# UpDuino_Camera_Adaptor_V2_0.net
KiCad netlist of a schematic drawn in Altium Designer
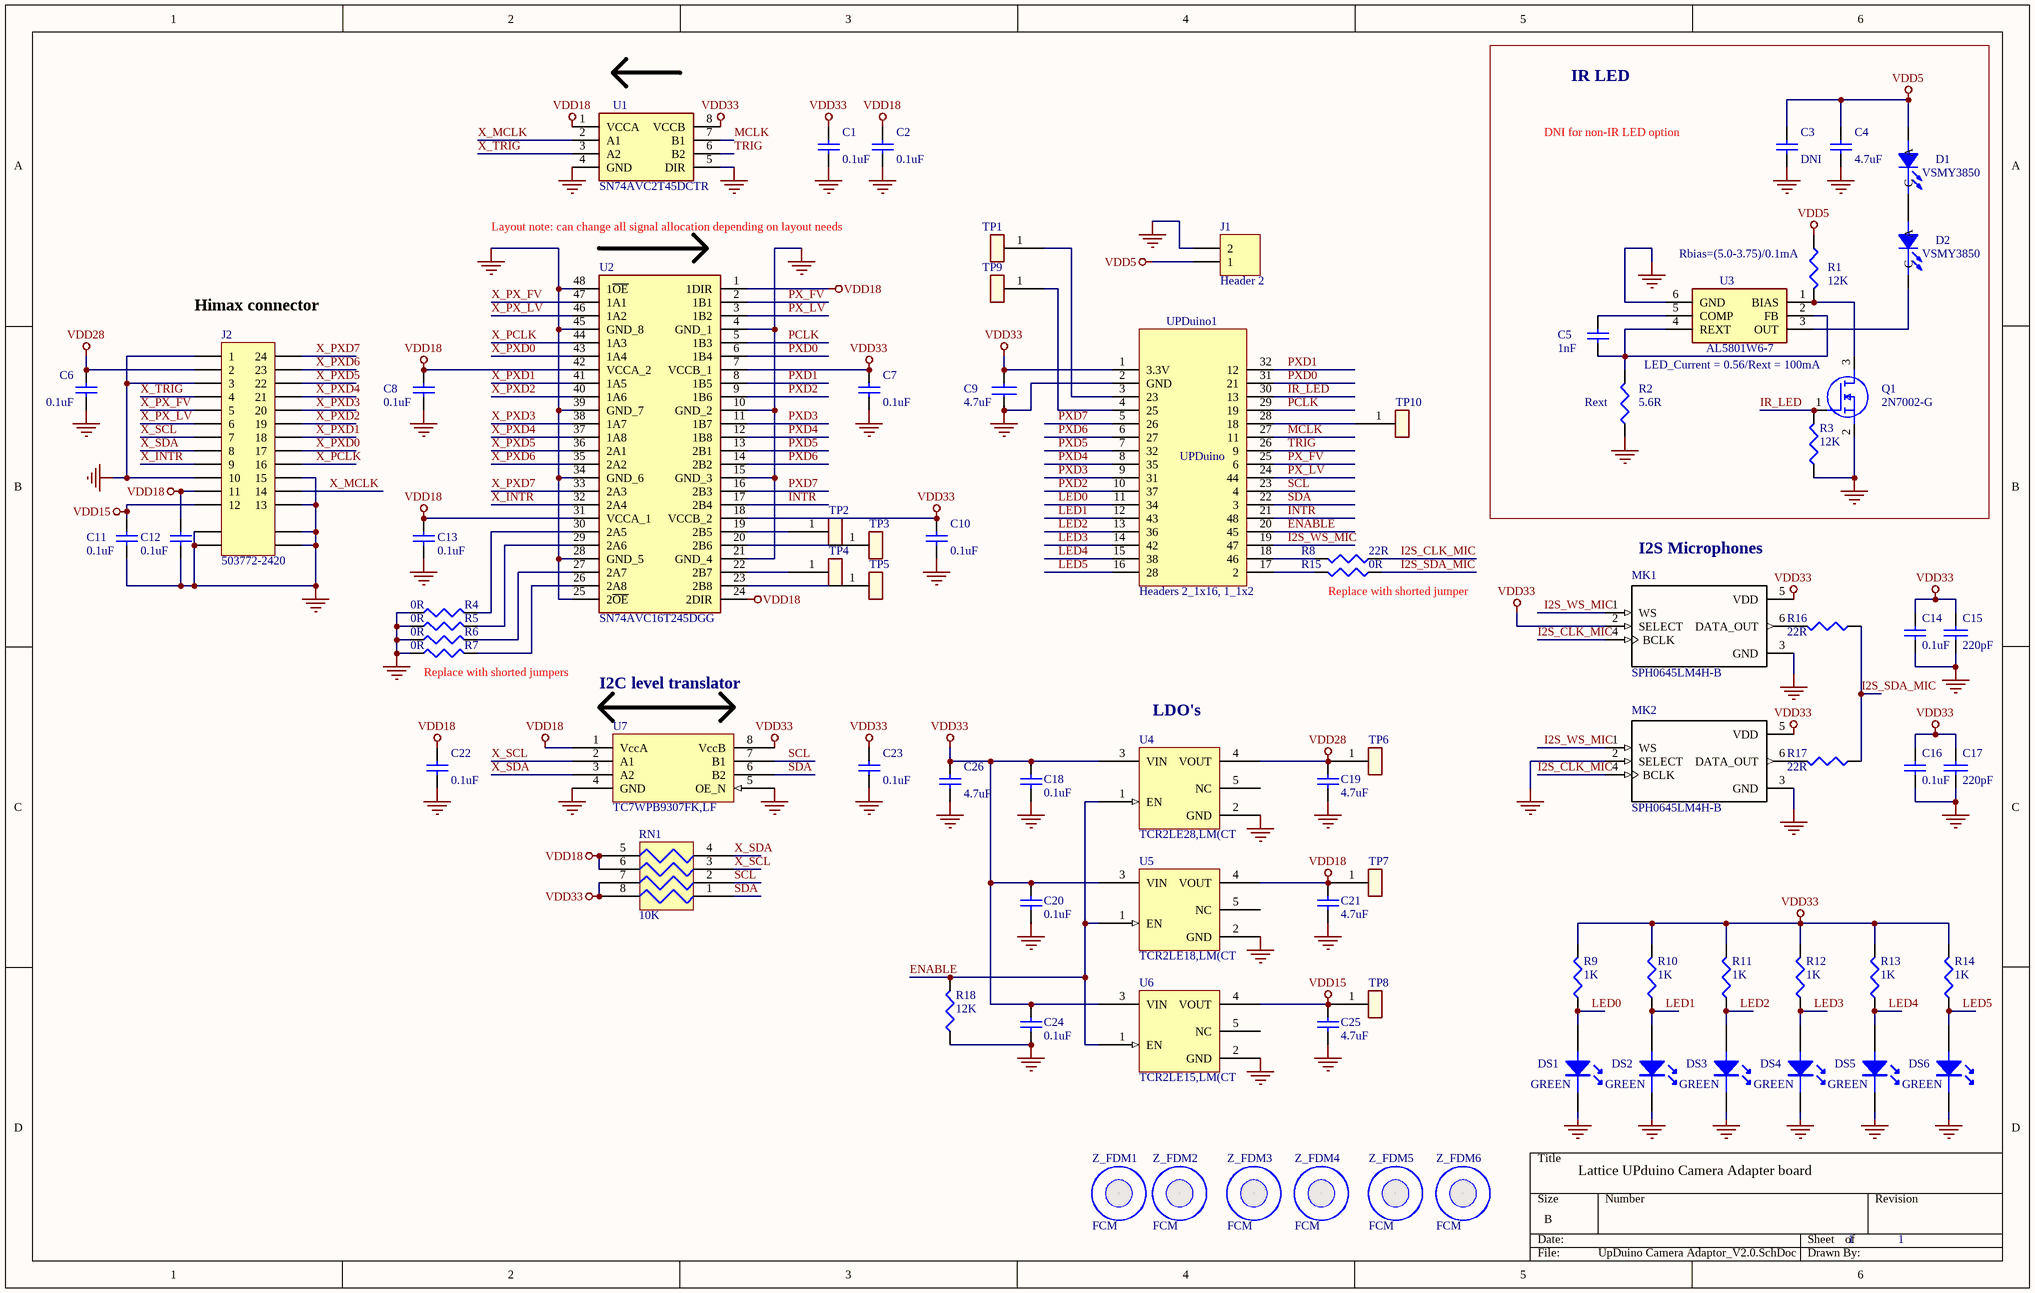
[diagram p0: UpDuino Camera Adaptor_V2.0.SchDoc]

(export (version "E")
  (design (tool "Eeschema 10.0.6"))
  (components
    (comp (ref "C1")
      (value "0.1uF")
      (footprint "C0603")
      (description "CAP CER 0.1UF 6.3V X5R 0603")
      (libsource (lib "MCD_Temp_LBE") (part "Cap_100nF_X7R_10%_0402"))
    )
    (comp (ref "C2")
      (value "0.1uF")
      (footprint "C0603")
      (description "CAP CER 0.1UF 6.3V X5R 0603")
      (libsource (lib "MCD_Temp_LBE") (part "Cap_100nF_X7R_10%_0402"))
    )
    (comp (ref "C3")
      (value "DNI")
      (footprint "C0603")
      (libsource (lib "MCD_Temp_LBE") (part "Cap_100nF_X7R_10%_0402"))
    )
    (comp (ref "C4")
      (value "4.7uF")
      (footprint "C0603")
      (description "CAP CER 4.7UF 6.3V X5R 0603")
      (libsource (lib "MCD_Temp_LBE") (part "Cap_100nF_X7R_10%_0402"))
    )
    (comp (ref "C5")
      (value "1nF")
      (footprint "C0603")
      (description "CAP CER 0.1UF 6.3V X5R 0402")
      (fields (field (name "MANUFACTURER") "TDK") (field (name "PART #") "E-CAP-003"))
      (libsource (lib "MCD_Temp_LBE") (part "Cap_100nF_X7R_10%_0402"))
    )
    (comp (ref "C6")
      (value "0.1uF")
      (footprint "C0603")
      (description "CAP CER 0.1UF 6.3V X5R 0603")
      (libsource (lib "MCD_Temp_LBE") (part "Cap_100nF_X7R_10%_0402"))
    )
    (comp (ref "C7")
      (value "0.1uF")
      (footprint "C0603")
      (description "CAP CER 0.1UF 6.3V X5R 0603")
      (libsource (lib "MCD_Temp_LBE") (part "Cap_100nF_X7R_10%_0402"))
    )
    (comp (ref "C8")
      (value "0.1uF")
      (footprint "C0603")
      (description "CAP CER 0.1UF 6.3V X5R 0402")
      (libsource (lib "MCD_Temp_LBE") (part "Cap_100nF_X7R_10%_0402"))
    )
    (comp (ref "C9")
      (value "4.7uF")
      (footprint "C0603")
      (description "4.7 uF 6.3V X5R")
      (libsource (lib "*") (part "CAP NP"))
    )
    (comp (ref "C10")
      (value "0.1uF")
      (footprint "C0603")
      (description "CAP CER 0.1UF 6.3V X5R 0603")
      (libsource (lib "MCD_Temp_LBE") (part "Cap_100nF_X7R_10%_0402"))
    )
    (comp (ref "C11")
      (value "0.1uF")
      (footprint "C0603")
      (description "CAP CER 0.1UF 6.3V X5R 0603")
      (libsource (lib "MCD_Temp_LBE") (part "Cap_100nF_X7R_10%_0402"))
    )
    (comp (ref "C12")
      (value "0.1uF")
      (footprint "C0603")
      (description "CAP CER 0.1UF 6.3V X5R 0603")
      (libsource (lib "MCD_Temp_LBE") (part "Cap_100nF_X7R_10%_0402"))
    )
    (comp (ref "C13")
      (value "0.1uF")
      (footprint "C0603")
      (description "CAP CER 0.1UF 6.3V X5R 0402")
      (libsource (lib "MCD_Temp_LBE") (part "Cap_100nF_X7R_10%_0402"))
    )
    (comp (ref "C14")
      (value "0.1uF")
      (footprint "C0603")
      (description "CAP CER 0.1UF 6.3V X5R 0603")
      (libsource (lib "MCD_Temp_LBE") (part "Cap_100nF_X7R_10%_0402"))
    )
    (comp (ref "C15") (value "220pF") (footprint "C0603") (libsource (lib "Main") (part "CAP")))
    (comp (ref "C16")
      (value "0.1uF")
      (footprint "C0603")
      (description "CAP CER 0.1UF 6.3V X5R 0603")
      (libsource (lib "MCD_Temp_LBE") (part "Cap_100nF_X7R_10%_0402"))
    )
    (comp (ref "C17") (value "220pF") (footprint "C0603") (libsource (lib "Main") (part "CAP")))
    (comp (ref "C18")
      (value "0.1uF")
      (footprint "C0603")
      (description "CAP CER 0.1UF 6.3V X5R 0603")
      (libsource (lib "MCD_Temp_LBE") (part "Cap_1uF_X5R_10%_6V3_0402"))
    )
    (comp (ref "C19")
      (value "4.7uF")
      (footprint "C0603")
      (description "CAP CER 4.7UF 6.3V X5R 0603")
      (libsource (lib "MCD_Temp_LBE") (part "Cap_1uF_X5R_10%_6V3_0402"))
    )
    (comp (ref "C20")
      (value "0.1uF")
      (footprint "C0603")
      (description "CAP CER 0.1UF 6.3V X5R 0603")
      (libsource (lib "MCD_Temp_LBE") (part "Cap_1uF_X5R_10%_6V3_0402"))
    )
    (comp (ref "C21")
      (value "4.7uF")
      (footprint "C0603")
      (description "CAP CER 4.7UF 6.3V X5R 0603")
      (libsource (lib "MCD_Temp_LBE") (part "Cap_1uF_X5R_10%_6V3_0402"))
    )
    (comp (ref "C22")
      (value "0.1uF")
      (footprint "C0603")
      (description "CAP CER 0.1UF 6.3V X5R 0603")
      (libsource (lib "MCD_Temp_LBE") (part "Cap_100nF_X7R_10%_0402"))
    )
    (comp (ref "C23")
      (value "0.1uF")
      (footprint "C0603")
      (description "CAP CER 0.1UF 6.3V X5R 0603")
      (libsource (lib "MCD_Temp_LBE") (part "Cap_100nF_X7R_10%_0402"))
    )
    (comp (ref "C24")
      (value "0.1uF")
      (footprint "C0603")
      (description "CAP CER 0.1UF 6.3V X5R 0603")
      (libsource (lib "MCD_Temp_LBE") (part "Cap_1uF_X5R_10%_6V3_0402"))
    )
    (comp (ref "C25")
      (value "4.7uF")
      (footprint "C0603")
      (description "CAP CER 4.7UF 6.3V X5R 0603")
      (libsource (lib "MCD_Temp_LBE") (part "Cap_1uF_X5R_10%_6V3_0402"))
    )
    (comp (ref "C26")
      (value "4.7uF")
      (footprint "C0603")
      (description "CAP CER 4.7UF 6.3V X5R 0603")
      (libsource (lib "MCD_Temp_LBE") (part "Cap_100nF_X7R_10%_0402"))
    )
    (comp (ref "D1")
      (value "VSMY3850")
      (footprint "PLCC-2")
      (description "EMITTER IR 850NM 70MA 3.20MM SMD")
      (fields
        (field (name "MANUFACTURER") "OSRAM Opto Semiconductors Inc.")
        (field (name "MANUFACTURER PART NUMBER") "VSMY12850")
      )
      (libsource (lib "TINYMODULE_Library") (part "LED"))
    )
    (comp (ref "D2")
      (value "VSMY3850")
      (footprint "PLCC-2")
      (description "EMITTER IR 850NM 70MA 3.20MM SMD")
      (fields
        (field (name "MANUFACTURER") "OSRAM Opto Semiconductors Inc.")
        (field (name "MANUFACTURER PART NUMBER") "VSMY12850")
      )
      (libsource (lib "TINYMODULE_Library") (part "LED"))
    )
    (comp (ref "DS1")
      (value "GREEN")
      (footprint "LED_0603_12")
      (description "Liteon LTST-C191KGKT")
      (fields (field (name "MANUFACTURER") "Avago Technologies US Inc.") (field (name "PART #") "E-MISC-005"))
      (libsource (lib "*") (part "LED_1"))
    )
    (comp (ref "DS2")
      (value "GREEN")
      (footprint "LED_0603_12")
      (description "Liteon LTST-C191KGKT")
      (fields (field (name "MANUFACTURER") "Avago Technologies US Inc.") (field (name "PART #") "E-MISC-005"))
      (libsource (lib "*") (part "LED_1"))
    )
    (comp (ref "DS3")
      (value "GREEN")
      (footprint "LED_0603_12")
      (description "Liteon LTST-C191KGKT")
      (fields (field (name "MANUFACTURER") "Avago Technologies US Inc.") (field (name "PART #") "E-MISC-005"))
      (libsource (lib "*") (part "LED_1"))
    )
    (comp (ref "DS4")
      (value "GREEN")
      (footprint "LED_0603_12")
      (description "Liteon LTST-C191KGKT")
      (fields (field (name "MANUFACTURER") "Avago Technologies US Inc.") (field (name "PART #") "E-MISC-005"))
      (libsource (lib "*") (part "LED_1"))
    )
    (comp (ref "DS5")
      (value "GREEN")
      (footprint "LED_0603_12")
      (description "Liteon LTST-C191KGKT")
      (fields (field (name "MANUFACTURER") "Avago Technologies US Inc.") (field (name "PART #") "E-MISC-005"))
      (libsource (lib "*") (part "LED_1"))
    )
    (comp (ref "DS6")
      (value "GREEN")
      (footprint "LED_0603_12")
      (description "Liteon LTST-C191KGKT")
      (fields (field (name "MANUFACTURER") "Avago Technologies US Inc.") (field (name "PART #") "E-MISC-005"))
      (libsource (lib "*") (part "LED_1"))
    )
    (comp (ref "J1")
      (value "Header 2")
      (footprint "HDR1X2")
      (description "Header, 2-Pin")
      (fields (field (name "PUBLISHER") "Altium Limited"))
      (libsource (lib "Miscellaneous Connectors") (part "Header 2"))
    )
    (comp (ref "J2")
      (value "503772-2420")
      (footprint "MOLEX-5037722410_MOLEX")
      (description "Header, 12-Pin, Dual row")
      (fields
        (field (name "MANUFACTURER") "Amphenol FCI")
        (field (name "MANUFACTURER PART NUMBER") "SFV24R-3STE1HLF")
        (field (name "PUBLISHER") "Altium Limited")
      )
      (libsource (lib "UpDuino Camera Adaptor_V2.0") (part "Header 12X2A"))
    )
    (comp (ref "MK1")
      (value "SPH0645LM4H-B")
      (footprint "*MIC_SPH0645LM4H-B")
      (description "Mic Mems Digital I2s Omni -26db")
      (fields (field (name "MFR") "Knowles") (field (name "DIGI-KEY_PART_NUMBER") "423-1405-1-ND"))
      (libsource (lib "SPH0645LM4H-B") (part "SPH0645LM4H-B"))
    )
    (comp (ref "MK2")
      (value "SPH0645LM4H-B")
      (footprint "*MIC_SPH0645LM4H-B")
      (description "Mic Mems Digital I2s Omni -26db")
      (fields (field (name "MFR") "Knowles") (field (name "DIGI-KEY_PART_NUMBER") "423-1405-1-ND"))
      (libsource (lib "SPH0645LM4H-B") (part "SPH0645LM4H-B"))
    )
    (comp (ref "Q1")
      (value "2N7002-G")
      (footprint "SOT23-3")
      (description "MOSFET (N-Channel)")
      (fields (field (name "MOUSER PART NUMBER") "750-2N7002-G"))
      (libsource (lib "*") (part "2N7002-G"))
    )
    (comp (ref "R1") (value "12K") (footprint "R0603") (libsource (lib "*") (part "R_SH")))
    (comp (ref "R2") (value "5.6R") (footprint "R0603") (libsource (lib "*") (part "R_SH")))
    (comp (ref "R3") (value "12K") (footprint "R0603") (libsource (lib "*") (part "R_SH")))
    (comp (ref "R4") (value "0R") (footprint "SB_0603") (libsource (lib "*") (part "R_SH")))
    (comp (ref "R5") (value "0R") (footprint "SB_0603") (libsource (lib "*") (part "R_SH")))
    (comp (ref "R6") (value "0R") (footprint "SB_0603") (libsource (lib "*") (part "R_SH")))
    (comp (ref "R7") (value "0R") (footprint "SB_0603") (libsource (lib "*") (part "R_SH")))
    (comp (ref "R8") (value "22R") (footprint "R0603") (libsource (lib "*") (part "R_SH")))
    (comp (ref "R9") (value "1K") (footprint "R0603") (libsource (lib "*") (part "R_SH")))
    (comp (ref "R10") (value "1K") (footprint "R0603") (libsource (lib "*") (part "R_SH")))
    (comp (ref "R11") (value "1K") (footprint "R0603") (libsource (lib "*") (part "R_SH")))
    (comp (ref "R12") (value "1K") (footprint "R0603") (libsource (lib "*") (part "R_SH")))
    (comp (ref "R13") (value "1K") (footprint "R0603") (libsource (lib "*") (part "R_SH")))
    (comp (ref "R14") (value "1K") (footprint "R0603") (libsource (lib "*") (part "R_SH")))
    (comp (ref "R15") (value "0R") (footprint "SB_0603") (libsource (lib "*") (part "R_SH")))
    (comp (ref "R16") (value "22R") (footprint "R0603") (libsource (lib "*") (part "R_SH")))
    (comp (ref "R17") (value "22R") (footprint "R0603") (libsource (lib "*") (part "R_SH")))
    (comp (ref "R18") (value "12K") (footprint "R0603") (libsource (lib "*") (part "R_SH")))
    (comp (ref "RN1")
      (value "10K")
      (footprint "RN4(0402)")
      (description "EXB-28V104JX")
      (libsource (lib "main") (part "EXB28V"))
    )
    (comp (ref "TP1") (value "TEST POINT") (footprint "TP_SMD_D1") (libsource (lib "") (part "TEST POINT_1")))
    (comp (ref "TP2") (value "TEST POINT") (footprint "TP_SMD_D1") (libsource (lib "*") (part "TEST POINT")))
    (comp (ref "TP3") (value "TEST POINT") (footprint "TP_SMD_D1") (libsource (lib "*") (part "TEST POINT")))
    (comp (ref "TP4") (value "TEST POINT") (footprint "TP_SMD_D1") (libsource (lib "*") (part "TEST POINT")))
    (comp (ref "TP5") (value "TEST POINT") (footprint "TP_SMD_D1") (libsource (lib "*") (part "TEST POINT")))
    (comp (ref "TP6") (value "TEST POINT") (footprint "TP_SMD_D1") (libsource (lib "*") (part "TEST POINT")))
    (comp (ref "TP7") (value "TEST POINT") (footprint "TP_SMD_D1") (libsource (lib "*") (part "TEST POINT")))
    (comp (ref "TP8") (value "TEST POINT") (footprint "TP_SMD_D1") (libsource (lib "*") (part "TEST POINT")))
    (comp (ref "TP9") (value "TEST POINT") (footprint "TP_SMD_D1") (libsource (lib "") (part "TEST POINT_1")))
    (comp (ref "TP10") (value "TEST POINT") (footprint "TP_SMD_D1") (libsource (lib "*") (part "TEST POINT")))
    (comp (ref "U1")
      (value "SN74AVC2T45DCTR")
      (footprint "MSOP-8(2.95x2.80)")
      (description "Integrated Circuit")
      (fields
        (field (name "MOUSER PART NUMBER") "595-SN74AVC2T45DCTR")
        (field (name "RS PART NUMBER") "8253432P")
      )
      (libsource (lib "*") (part "SN74AVC2T45DCTR"))
    )
    (comp (ref "U2")
      (value "SN74AVC16T245DGG")
      (footprint "TSSOP-48")
      (description "Integrated Circuit")
      (fields (field (name "MOUSER PART NUMBER") "595-SN74AVC16T245DG"))
      (libsource (lib "*") (part "SN74AVC16T245DGG"))
    )
    (comp (ref "U3")
      (value "AL5801W6-7")
      (footprint "SOT-23-6-(SSOT-6)")
      (description "Integrated Circuit")
      (fields (field (name "MOUSER PART NUMBER") "621-AL5801W6-7") (field (name "RS PART NUMBER") "8228732P"))
      (libsource (lib "*") (part "AL5801W6-7"))
    )
    (comp (ref "U4")
      (value "TCR2LE28,LM(CT")
      (footprint "SOT-553")
      (libsource (lib "TINYMODULE") (part "TCR2LE12ESV"))
    )
    (comp (ref "U5")
      (value "TCR2LE18,LM(CT")
      (footprint "SOT-553")
      (libsource (lib "TINYMODULE") (part "TCR2LE12ESV"))
    )
    (comp (ref "U6")
      (value "TCR2LE15,LM(CT")
      (footprint "SOT-553")
      (libsource (lib "TINYMODULE") (part "TCR2LE12ESV"))
    )
    (comp (ref "U7")
      (value "TC7WPB9307FK,LF")
      (footprint "SSOP8-P-0.50A")
      (description "Dual bidirectional level translator")
      (libsource (lib "tinyVision") (part "TC7WPB9307FK"))
    )
    (comp (ref "UPDuino1")
      (value "Headers 2_1x16, 1_1x2")
      (footprint "UPDuino-SMD")
      (description "UPDuino Breakout Headers")
      (fields (field (name "MFR PART NO.") "HWS15774, HWS15768") (field (name "MFR") "Phoenix contact"))
      (libsource (lib "one_wire") (part "UPDuino_Breakout"))
    )
    (comp (ref "Z_FDM1") (value "FCM") (footprint "FID100X250N") (libsource (lib "LCD-TN43") (part "FCM")))
    (comp (ref "Z_FDM2") (value "FCM") (footprint "FID100X250N") (libsource (lib "LCD-TN43") (part "FCM")))
    (comp (ref "Z_FDM3") (value "FCM") (footprint "FID100X250N") (libsource (lib "LCD-TN43") (part "FCM")))
    (comp (ref "Z_FDM4") (value "FCM") (footprint "FID100X250N") (libsource (lib "LCD-TN43") (part "FCM")))
    (comp (ref "Z_FDM5") (value "FCM") (footprint "FID100X250N") (libsource (lib "LCD-TN43") (part "FCM")))
    (comp (ref "Z_FDM6") (value "FCM") (footprint "FID100X250N") (libsource (lib "LCD-TN43") (part "FCM")))
  )
  (nets
    (net (code "1") (name "/ENABLE") (class "Default")
      (node (ref "R18") (pin "2") (pinfunction "2_2") (pintype "passive"))
      (node (ref "U4") (pin "1") (pinfunction "EN_1") (pintype "input"))
      (node (ref "U5") (pin "1") (pinfunction "EN_1") (pintype "input"))
      (node (ref "U6") (pin "1") (pinfunction "EN_1") (pintype "input"))
      (node (ref "UPDuino1") (pin "20") (pinfunction "45_20") (pintype "passive"))
    )
    (net (code "2") (name "/I2S_CLK_MIC") (class "Default")
      (node (ref "MK1") (pin "4") (pinfunction "BCLK_4") (pintype "input"))
      (node (ref "MK2") (pin "4") (pinfunction "BCLK_4") (pintype "input"))
      (node (ref "R8") (pin "1") (pinfunction "1_1") (pintype "passive"))
    )
    (net (code "3") (name "/I2S_SDA_MIC") (class "Default")
      (node (ref "R15") (pin "1") (pinfunction "1_1") (pintype "passive"))
      (node (ref "R16") (pin "1") (pinfunction "1_1") (pintype "passive"))
      (node (ref "R17") (pin "1") (pinfunction "1_1") (pintype "passive"))
    )
    (net (code "4") (name "/I2S_WS_MIC") (class "Default")
      (node (ref "MK1") (pin "1") (pinfunction "WS_1") (pintype "input"))
      (node (ref "MK2") (pin "1") (pinfunction "WS_1") (pintype "input"))
      (node (ref "UPDuino1") (pin "19") (pinfunction "47_19") (pintype "passive"))
    )
    (net (code "5") (name "/INTR") (class "Default")
      (node (ref "U2") (pin "17") (pinfunction "2B4_17") (pintype "passive"))
      (node (ref "UPDuino1") (pin "21") (pinfunction "48_21") (pintype "passive"))
    )
    (net (code "6") (name "/IR_LED") (class "Default")
      (node (ref "Q1") (pin "1") (pinfunction "G_1") (pintype "passive"))
      (node (ref "R3") (pin "2") (pinfunction "2_2") (pintype "passive"))
      (node (ref "UPDuino1") (pin "30") (pinfunction "13_30") (pintype "passive"))
    )
    (net (code "7") (name "/LED0") (class "Default")
      (node (ref "DS1") (pin "1") (pinfunction "1_1") (pintype "passive"))
      (node (ref "R9") (pin "1") (pinfunction "1_1") (pintype "passive"))
      (node (ref "UPDuino1") (pin "11") (pinfunction "34_11") (pintype "passive"))
    )
    (net (code "8") (name "/LED1") (class "Default")
      (node (ref "DS2") (pin "1") (pinfunction "1_1") (pintype "passive"))
      (node (ref "R10") (pin "1") (pinfunction "1_1") (pintype "passive"))
      (node (ref "UPDuino1") (pin "12") (pinfunction "43_12") (pintype "passive"))
    )
    (net (code "9") (name "/LED2") (class "Default")
      (node (ref "DS3") (pin "1") (pinfunction "1_1") (pintype "passive"))
      (node (ref "R11") (pin "1") (pinfunction "1_1") (pintype "passive"))
      (node (ref "UPDuino1") (pin "13") (pinfunction "36_13") (pintype "passive"))
    )
    (net (code "10") (name "/LED3") (class "Default")
      (node (ref "DS4") (pin "1") (pinfunction "1_1") (pintype "passive"))
      (node (ref "R12") (pin "1") (pinfunction "1_1") (pintype "passive"))
      (node (ref "UPDuino1") (pin "14") (pinfunction "42_14") (pintype "passive"))
    )
    (net (code "11") (name "/LED4") (class "Default")
      (node (ref "DS5") (pin "1") (pinfunction "1_1") (pintype "passive"))
      (node (ref "R13") (pin "1") (pinfunction "1_1") (pintype "passive"))
      (node (ref "UPDuino1") (pin "15") (pinfunction "38_15") (pintype "passive"))
    )
    (net (code "12") (name "/LED5") (class "Default")
      (node (ref "DS6") (pin "1") (pinfunction "1_1") (pintype "passive"))
      (node (ref "R14") (pin "1") (pinfunction "1_1") (pintype "passive"))
      (node (ref "UPDuino1") (pin "16") (pinfunction "28_16") (pintype "passive"))
    )
    (net (code "13") (name "/MCLK") (class "Default")
      (node (ref "U1") (pin "7") (pinfunction "B1_7") (pintype "passive"))
      (node (ref "UPDuino1") (pin "27") (pinfunction "11_27") (pintype "passive"))
    )
    (net (code "14") (name "/PCLK") (class "Default")
      (node (ref "U2") (pin "5") (pinfunction "1B3_5") (pintype "passive"))
      (node (ref "UPDuino1") (pin "29") (pinfunction "19_29") (pintype "passive"))
    )
    (net (code "15") (name "/PXD0") (class "Default")
      (node (ref "U2") (pin "6") (pinfunction "1B4_6") (pintype "passive"))
      (node (ref "UPDuino1") (pin "31") (pinfunction "21_31") (pintype "passive"))
    )
    (net (code "16") (name "/PXD1") (class "Default")
      (node (ref "U2") (pin "8") (pinfunction "1B5_8") (pintype "passive"))
      (node (ref "UPDuino1") (pin "32") (pinfunction "12_32") (pintype "passive"))
    )
    (net (code "17") (name "/PXD2") (class "Default")
      (node (ref "U2") (pin "9") (pinfunction "1B6_9") (pintype "passive"))
      (node (ref "UPDuino1") (pin "10") (pinfunction "37_10") (pintype "passive"))
    )
    (net (code "18") (name "/PXD3") (class "Default")
      (node (ref "U2") (pin "11") (pinfunction "1B7_11") (pintype "passive"))
      (node (ref "UPDuino1") (pin "9") (pinfunction "31_9") (pintype "passive"))
    )
    (net (code "19") (name "/PXD4") (class "Default")
      (node (ref "U2") (pin "12") (pinfunction "1B8_12") (pintype "passive"))
      (node (ref "UPDuino1") (pin "8") (pinfunction "35_8") (pintype "passive"))
    )
    (net (code "20") (name "/PXD5") (class "Default")
      (node (ref "U2") (pin "13") (pinfunction "2B1_13") (pintype "passive"))
      (node (ref "UPDuino1") (pin "7") (pinfunction "32_7") (pintype "passive"))
    )
    (net (code "21") (name "/PXD6") (class "Default")
      (node (ref "U2") (pin "14") (pinfunction "2B2_14") (pintype "passive"))
      (node (ref "UPDuino1") (pin "6") (pinfunction "27_6") (pintype "passive"))
    )
    (net (code "22") (name "/PXD7") (class "Default")
      (node (ref "U2") (pin "16") (pinfunction "2B3_16") (pintype "passive"))
      (node (ref "UPDuino1") (pin "5") (pinfunction "26_5") (pintype "passive"))
    )
    (net (code "23") (name "/PX_FV") (class "Default")
      (node (ref "U2") (pin "2") (pinfunction "1B1_2") (pintype "passive"))
      (node (ref "UPDuino1") (pin "25") (pinfunction "6_25") (pintype "passive"))
    )
    (net (code "24") (name "/PX_LV") (class "Default")
      (node (ref "U2") (pin "3") (pinfunction "1B2_3") (pintype "passive"))
      (node (ref "UPDuino1") (pin "24") (pinfunction "44_24") (pintype "passive"))
    )
    (net (code "25") (name "/SCL") (class "Default")
      (node (ref "RN1") (pin "2") (pintype "passive"))
      (node (ref "U7") (pin "7") (pinfunction "B1_7") (pintype "passive"))
      (node (ref "UPDuino1") (pin "23") (pinfunction "4_23") (pintype "passive"))
    )
    (net (code "26") (name "/SDA") (class "Default")
      (node (ref "RN1") (pin "1") (pintype "passive"))
      (node (ref "U7") (pin "6") (pinfunction "B2_6") (pintype "passive"))
      (node (ref "UPDuino1") (pin "22") (pinfunction "3_22") (pintype "passive"))
    )
    (net (code "27") (name "/TRIG") (class "Default")
      (node (ref "U1") (pin "6") (pinfunction "B2_6") (pintype "passive"))
      (node (ref "UPDuino1") (pin "26") (pinfunction "9_26") (pintype "passive"))
    )
    (net (code "28") (name "/X_INTR") (class "Default")
      (node (ref "J2") (pin "9") (pinfunction "9_9") (pintype "passive"))
      (node (ref "U2") (pin "32") (pinfunction "2A4_32") (pintype "passive"))
    )
    (net (code "29") (name "/X_MCLK") (class "Default")
      (node (ref "J2") (pin "14") (pinfunction "14_14") (pintype "passive"))
      (node (ref "U1") (pin "2") (pinfunction "A1_2") (pintype "passive"))
    )
    (net (code "30") (name "/X_PCLK") (class "Default")
      (node (ref "J2") (pin "16") (pinfunction "16_16") (pintype "passive"))
      (node (ref "U2") (pin "44") (pinfunction "1A3_44") (pintype "passive"))
    )
    (net (code "31") (name "/X_PXD0") (class "Default")
      (node (ref "J2") (pin "17") (pinfunction "17_17") (pintype "passive"))
      (node (ref "U2") (pin "43") (pinfunction "1A4_43") (pintype "passive"))
    )
    (net (code "32") (name "/X_PXD1") (class "Default")
      (node (ref "J2") (pin "18") (pinfunction "18_18") (pintype "passive"))
      (node (ref "U2") (pin "41") (pinfunction "1A5_41") (pintype "passive"))
    )
    (net (code "33") (name "/X_PXD2") (class "Default")
      (node (ref "J2") (pin "19") (pinfunction "19_19") (pintype "passive"))
      (node (ref "U2") (pin "40") (pinfunction "1A6_40") (pintype "passive"))
    )
    (net (code "34") (name "/X_PXD3") (class "Default")
      (node (ref "J2") (pin "20") (pinfunction "20_20") (pintype "passive"))
      (node (ref "U2") (pin "38") (pinfunction "1A7_38") (pintype "passive"))
    )
    (net (code "35") (name "/X_PXD4") (class "Default")
      (node (ref "J2") (pin "21") (pinfunction "21_21") (pintype "passive"))
      (node (ref "U2") (pin "37") (pinfunction "1A8_37") (pintype "passive"))
    )
    (net (code "36") (name "/X_PXD5") (class "Default")
      (node (ref "J2") (pin "22") (pinfunction "22_22") (pintype "passive"))
      (node (ref "U2") (pin "36") (pinfunction "2A1_36") (pintype "passive"))
    )
    (net (code "37") (name "/X_PXD6") (class "Default")
      (node (ref "J2") (pin "23") (pinfunction "23_23") (pintype "passive"))
      (node (ref "U2") (pin "35") (pinfunction "2A2_35") (pintype "passive"))
    )
    (net (code "38") (name "/X_PXD7") (class "Default")
      (node (ref "J2") (pin "24") (pinfunction "24_24") (pintype "passive"))
      (node (ref "U2") (pin "33") (pinfunction "2A3_33") (pintype "passive"))
    )
    (net (code "39") (name "/X_PX_FV") (class "Default")
      (node (ref "J2") (pin "5") (pinfunction "5_5") (pintype "passive"))
      (node (ref "U2") (pin "47") (pinfunction "1A1_47") (pintype "passive"))
    )
    (net (code "40") (name "/X_PX_LV") (class "Default")
      (node (ref "J2") (pin "6") (pinfunction "6_6") (pintype "passive"))
      (node (ref "U2") (pin "46") (pinfunction "1A2_46") (pintype "passive"))
    )
    (net (code "41") (name "/X_SCL") (class "Default")
      (node (ref "J2") (pin "7") (pinfunction "7_7") (pintype "passive"))
      (node (ref "RN1") (pin "3") (pintype "passive"))
      (node (ref "U7") (pin "2") (pinfunction "A1_2") (pintype "passive"))
    )
    (net (code "42") (name "/X_SDA") (class "Default")
      (node (ref "J2") (pin "8") (pinfunction "8_8") (pintype "passive"))
      (node (ref "RN1") (pin "4") (pintype "passive"))
      (node (ref "U7") (pin "3") (pinfunction "A2_3") (pintype "passive"))
    )
    (net (code "43") (name "/X_TRIG") (class "Default")
      (node (ref "J2") (pin "4") (pinfunction "4_4") (pintype "passive"))
      (node (ref "U1") (pin "3") (pinfunction "A2_3") (pintype "passive"))
    )
    (net (code "44") (name "GND") (class "Default")
      (node (ref "C1") (pin "2") (pinfunction "2_2") (pintype "passive"))
      (node (ref "C10") (pin "2") (pinfunction "2_2") (pintype "passive"))
      (node (ref "C11") (pin "2") (pinfunction "2_2") (pintype "passive"))
      (node (ref "C12") (pin "2") (pinfunction "2_2") (pintype "passive"))
      (node (ref "C13") (pin "2") (pinfunction "2_2") (pintype "passive"))
      (node (ref "C14") (pin "2") (pinfunction "2_2") (pintype "passive"))
      (node (ref "C15") (pin "2") (pinfunction "2_2") (pintype "passive"))
      (node (ref "C16") (pin "2") (pinfunction "2_2") (pintype "passive"))
      (node (ref "C17") (pin "2") (pinfunction "2_2") (pintype "passive"))
      (node (ref "C18") (pin "1") (pinfunction "1_1") (pintype "passive"))
      (node (ref "C19") (pin "1") (pinfunction "1_1") (pintype "passive"))
      (node (ref "C2") (pin "2") (pinfunction "2_2") (pintype "passive"))
      (node (ref "C20") (pin "1") (pinfunction "1_1") (pintype "passive"))
      (node (ref "C21") (pin "1") (pinfunction "1_1") (pintype "passive"))
      (node (ref "C22") (pin "2") (pinfunction "2_2") (pintype "passive"))
      (node (ref "C23") (pin "2") (pinfunction "2_2") (pintype "passive"))
      (node (ref "C24") (pin "1") (pinfunction "1_1") (pintype "passive"))
      (node (ref "C25") (pin "1") (pinfunction "1_1") (pintype "passive"))
      (node (ref "C26") (pin "2") (pinfunction "2_2") (pintype "passive"))
      (node (ref "C3") (pin "2") (pinfunction "2_2") (pintype "passive"))
      (node (ref "C4") (pin "2") (pinfunction "2_2") (pintype "passive"))
      (node (ref "C6") (pin "2") (pinfunction "2_2") (pintype "passive"))
      (node (ref "C7") (pin "2") (pinfunction "2_2") (pintype "passive"))
      (node (ref "C8") (pin "2") (pinfunction "2_2") (pintype "passive"))
      (node (ref "C9") (pin "1") (pinfunction "1_1") (pintype "passive"))
      (node (ref "DS1") (pin "2") (pinfunction "2_2") (pintype "passive"))
      (node (ref "DS2") (pin "2") (pinfunction "2_2") (pintype "passive"))
      (node (ref "DS3") (pin "2") (pinfunction "2_2") (pintype "passive"))
      (node (ref "DS4") (pin "2") (pinfunction "2_2") (pintype "passive"))
      (node (ref "DS5") (pin "2") (pinfunction "2_2") (pintype "passive"))
      (node (ref "DS6") (pin "2") (pinfunction "2_2") (pintype "passive"))
      (node (ref "J1") (pin "2") (pinfunction "2_2") (pintype "passive"))
      (node (ref "J2") (pin "1") (pinfunction "1_1") (pintype "passive"))
      (node (ref "J2") (pin "10") (pinfunction "10_10") (pintype "passive"))
      (node (ref "J2") (pin "13") (pinfunction "13_13") (pintype "passive"))
      (node (ref "J2") (pin "15") (pinfunction "15_15") (pintype "passive"))
      (node (ref "J2") (pin "3") (pinfunction "3_3") (pintype "passive"))
      (node (ref "J2") (pin "GND1") (pinfunction "GND1_GND1") (pintype "passive"))
      (node (ref "J2") (pin "GND2") (pinfunction "GND2_GND2") (pintype "passive"))
      (node (ref "J2") (pin "GND3") (pinfunction "GND3_GND3") (pintype "passive"))
      (node (ref "J2") (pin "GND4") (pinfunction "GND4_GND4") (pintype "passive"))
      (node (ref "MK1") (pin "3") (pinfunction "GND_3") (pintype "power_in"))
      (node (ref "MK2") (pin "2") (pinfunction "SELECT_2") (pintype "input"))
      (node (ref "MK2") (pin "3") (pinfunction "GND_3") (pintype "power_in"))
      (node (ref "Q1") (pin "2") (pinfunction "S_2") (pintype "passive"))
      (node (ref "R18") (pin "1") (pinfunction "1_1") (pintype "passive"))
      (node (ref "R2") (pin "2") (pinfunction "2_2") (pintype "passive"))
      (node (ref "R3") (pin "1") (pinfunction "1_1") (pintype "passive"))
      (node (ref "R4") (pin "2") (pinfunction "2_2") (pintype "passive"))
      (node (ref "R5") (pin "2") (pinfunction "2_2") (pintype "passive"))
      (node (ref "R6") (pin "2") (pinfunction "2_2") (pintype "passive"))
      (node (ref "R7") (pin "2") (pinfunction "2_2") (pintype "passive"))
      (node (ref "U1") (pin "4") (pinfunction "GND_4") (pintype "power_in"))
      (node (ref "U1") (pin "5") (pinfunction "DIR_5") (pintype "passive"))
      (node (ref "U2") (pin "10") (pinfunction "GND_2_10") (pintype "passive"))
      (node (ref "U2") (pin "15") (pinfunction "GND_3_15") (pintype "passive"))
      (node (ref "U2") (pin "21") (pinfunction "GND_4_21") (pintype "passive"))
      (node (ref "U2") (pin "25") (pinfunction "2~{OE}_25") (pintype "passive"))
      (node (ref "U2") (pin "28") (pinfunction "GND_5_28") (pintype "passive"))
      (node (ref "U2") (pin "34") (pinfunction "GND_6_34") (pintype "passive"))
      (node (ref "U2") (pin "39") (pinfunction "GND_7_39") (pintype "passive"))
      (node (ref "U2") (pin "4") (pinfunction "GND_1_4") (pintype "passive"))
      (node (ref "U2") (pin "45") (pinfunction "GND_8_45") (pintype "passive"))
      (node (ref "U2") (pin "48") (pinfunction "1~{OE}_48") (pintype "passive"))
      (node (ref "U3") (pin "6") (pinfunction "GND_6") (pintype "passive"))
      (node (ref "U4") (pin "2") (pinfunction "GND_2") (pintype "power_in"))
      (node (ref "U5") (pin "2") (pinfunction "GND_2") (pintype "power_in"))
      (node (ref "U6") (pin "2") (pinfunction "GND_2") (pintype "power_in"))
      (node (ref "U7") (pin "4") (pinfunction "GND_4") (pintype "power_in"))
      (node (ref "U7") (pin "5") (pinfunction "OE_N_5") (pintype "input"))
      (node (ref "UPDuino1") (pin "2") (pinfunction "GND_2") (pintype "passive"))
    )
    (net (code "45") (name "Net-(D1-PadC)") (class "Default")
      (node (ref "D1") (pin "C") (pinfunction "C_C") (pintype "passive"))
      (node (ref "D2") (pin "A") (pinfunction "A_A") (pintype "passive"))
    )
    (net (code "46") (name "Net-(MK1-DATA_OUT)") (class "Default")
      (node (ref "MK1") (pin "6") (pinfunction "DATA_OUT_6") (pintype "output"))
      (node (ref "R16") (pin "2") (pinfunction "2_2") (pintype "passive"))
    )
    (net (code "47") (name "Net-(MK2-DATA_OUT)") (class "Default")
      (node (ref "MK2") (pin "6") (pinfunction "DATA_OUT_6") (pintype "output"))
      (node (ref "R17") (pin "2") (pinfunction "2_2") (pintype "passive"))
    )
    (net (code "48") (name "Net-(Q1-D)") (class "Default")
      (node (ref "Q1") (pin "3") (pinfunction "D_3") (pintype "passive"))
      (node (ref "R1") (pin "1") (pinfunction "1_1") (pintype "passive"))
      (node (ref "U3") (pin "1") (pinfunction "BIAS_1") (pintype "passive"))
    )
    (net (code "49") (name "Net-(U2-2A5)") (class "Default")
      (node (ref "R4") (pin "1") (pinfunction "1_1") (pintype "passive"))
      (node (ref "U2") (pin "30") (pinfunction "2A5_30") (pintype "passive"))
    )
    (net (code "50") (name "Net-(U2-2A6)") (class "Default")
      (node (ref "R5") (pin "1") (pinfunction "1_1") (pintype "passive"))
      (node (ref "U2") (pin "29") (pinfunction "2A6_29") (pintype "passive"))
    )
    (net (code "51") (name "Net-(U2-2A7)") (class "Default")
      (node (ref "R6") (pin "1") (pinfunction "1_1") (pintype "passive"))
      (node (ref "U2") (pin "27") (pinfunction "2A7_27") (pintype "passive"))
    )
    (net (code "52") (name "Net-(U2-2A8)") (class "Default")
      (node (ref "R7") (pin "1") (pinfunction "1_1") (pintype "passive"))
      (node (ref "U2") (pin "26") (pinfunction "2A8_26") (pintype "passive"))
    )
    (net (code "53") (name "Net-(U2-2B5)") (class "Default")
      (node (ref "TP2") (pin "1") (pinfunction "1_1") (pintype "passive"))
      (node (ref "U2") (pin "19") (pinfunction "2B5_19") (pintype "passive"))
    )
    (net (code "54") (name "Net-(U2-2B6)") (class "Default")
      (node (ref "TP3") (pin "1") (pinfunction "1_1") (pintype "passive"))
      (node (ref "U2") (pin "20") (pinfunction "2B6_20") (pintype "passive"))
    )
    (net (code "55") (name "Net-(U2-2B7)") (class "Default")
      (node (ref "TP4") (pin "1") (pinfunction "1_1") (pintype "passive"))
      (node (ref "U2") (pin "22") (pinfunction "2B7_22") (pintype "passive"))
    )
    (net (code "56") (name "Net-(U2-2B8)") (class "Default")
      (node (ref "TP5") (pin "1") (pinfunction "1_1") (pintype "passive"))
      (node (ref "U2") (pin "23") (pinfunction "2B8_23") (pintype "passive"))
    )
    (net (code "57") (name "Net-(U3-COMP)") (class "Default")
      (node (ref "C5") (pin "1") (pinfunction "1_1") (pintype "passive"))
      (node (ref "U3") (pin "5") (pinfunction "COMP_5") (pintype "passive"))
    )
    (net (code "58") (name "Net-(U3-FB)") (class "Default")
      (node (ref "C5") (pin "2") (pinfunction "2_2") (pintype "passive"))
      (node (ref "R2") (pin "1") (pinfunction "1_1") (pintype "passive"))
      (node (ref "U3") (pin "2") (pinfunction "FB_2") (pintype "passive"))
      (node (ref "U3") (pin "4") (pinfunction "REXT_4") (pintype "passive"))
    )
    (net (code "59") (name "Net-(U3-OUT)") (class "Default")
      (node (ref "D2") (pin "C") (pinfunction "C_C") (pintype "passive"))
      (node (ref "U3") (pin "3") (pinfunction "OUT_3") (pintype "passive"))
    )
    (net (code "60") (name "Net-(UPDuino1-2)") (class "Default")
      (node (ref "R15") (pin "2") (pinfunction "2_2") (pintype "passive"))
      (node (ref "UPDuino1") (pin "17") (pinfunction "2_17") (pintype "passive"))
    )
    (net (code "61") (name "Net-(UPDuino1-18)") (class "Default")
      (node (ref "TP10") (pin "1") (pinfunction "1_1") (pintype "passive"))
      (node (ref "UPDuino1") (pin "28") (pinfunction "18_28") (pintype "passive"))
    )
    (net (code "62") (name "Net-(UPDuino1-23)") (class "Default")
      (node (ref "TP1") (pin "1") (pinfunction "1_1") (pintype "passive"))
      (node (ref "UPDuino1") (pin "3") (pinfunction "23_3") (pintype "passive"))
    )
    (net (code "63") (name "Net-(UPDuino1-25)") (class "Default")
      (node (ref "TP9") (pin "1") (pinfunction "1_1") (pintype "passive"))
      (node (ref "UPDuino1") (pin "4") (pinfunction "25_4") (pintype "passive"))
    )
    (net (code "64") (name "Net-(UPDuino1-46)") (class "Default")
      (node (ref "R8") (pin "2") (pinfunction "2_2") (pintype "passive"))
      (node (ref "UPDuino1") (pin "18") (pinfunction "46_18") (pintype "passive"))
    )
    (net (code "65") (name "VDD5") (class "Default")
      (node (ref "C3") (pin "1") (pinfunction "1_1") (pintype "passive"))
      (node (ref "C4") (pin "1") (pinfunction "1_1") (pintype "passive"))
      (node (ref "D1") (pin "A") (pinfunction "A_A") (pintype "passive"))
      (node (ref "J1") (pin "1") (pinfunction "1_1") (pintype "passive"))
      (node (ref "R1") (pin "2") (pinfunction "2_2") (pintype "passive"))
    )
    (net (code "66") (name "VDD15") (class "Default")
      (node (ref "C11") (pin "1") (pinfunction "1_1") (pintype "passive"))
      (node (ref "C25") (pin "2") (pinfunction "2_2") (pintype "passive"))
      (node (ref "J2") (pin "12") (pinfunction "12_12") (pintype "passive"))
      (node (ref "TP8") (pin "1") (pinfunction "1_1") (pintype "passive"))
      (node (ref "U6") (pin "4") (pinfunction "VOUT_4") (pintype "power_in"))
    )
    (net (code "67") (name "VDD18") (class "Default")
      (node (ref "C12") (pin "1") (pinfunction "1_1") (pintype "passive"))
      (node (ref "C13") (pin "1") (pinfunction "1_1") (pintype "passive"))
      (node (ref "C2") (pin "1") (pinfunction "1_1") (pintype "passive"))
      (node (ref "C21") (pin "2") (pinfunction "2_2") (pintype "passive"))
      (node (ref "C22") (pin "1") (pinfunction "1_1") (pintype "passive"))
      (node (ref "C8") (pin "1") (pinfunction "1_1") (pintype "passive"))
      (node (ref "J2") (pin "11") (pinfunction "11_11") (pintype "passive"))
      (node (ref "RN1") (pin "5") (pintype "passive"))
      (node (ref "RN1") (pin "6") (pintype "passive"))
      (node (ref "TP7") (pin "1") (pinfunction "1_1") (pintype "passive"))
      (node (ref "U1") (pin "1") (pinfunction "VCCA_1") (pintype "power_in"))
      (node (ref "U2") (pin "1") (pinfunction "1DIR_1") (pintype "passive"))
      (node (ref "U2") (pin "24") (pinfunction "2DIR_24") (pintype "passive"))
      (node (ref "U2") (pin "31") (pinfunction "VCCA_1_31") (pintype "passive"))
      (node (ref "U2") (pin "42") (pinfunction "VCCA_2_42") (pintype "passive"))
      (node (ref "U5") (pin "4") (pinfunction "VOUT_4") (pintype "power_in"))
      (node (ref "U7") (pin "1") (pinfunction "VccA_1") (pintype "power_in"))
    )
    (net (code "68") (name "VDD28") (class "Default")
      (node (ref "C19") (pin "2") (pinfunction "2_2") (pintype "passive"))
      (node (ref "C6") (pin "1") (pinfunction "1_1") (pintype "passive"))
      (node (ref "J2") (pin "2") (pinfunction "2_2") (pintype "passive"))
      (node (ref "TP6") (pin "1") (pinfunction "1_1") (pintype "passive"))
      (node (ref "U4") (pin "4") (pinfunction "VOUT_4") (pintype "power_in"))
    )
    (net (code "69") (name "VDD33") (class "Default")
      (node (ref "C1") (pin "1") (pinfunction "1_1") (pintype "passive"))
      (node (ref "C10") (pin "1") (pinfunction "1_1") (pintype "passive"))
      (node (ref "C14") (pin "1") (pinfunction "1_1") (pintype "passive"))
      (node (ref "C15") (pin "1") (pinfunction "1_1") (pintype "passive"))
      (node (ref "C16") (pin "1") (pinfunction "1_1") (pintype "passive"))
      (node (ref "C17") (pin "1") (pinfunction "1_1") (pintype "passive"))
      (node (ref "C18") (pin "2") (pinfunction "2_2") (pintype "passive"))
      (node (ref "C20") (pin "2") (pinfunction "2_2") (pintype "passive"))
      (node (ref "C23") (pin "1") (pinfunction "1_1") (pintype "passive"))
      (node (ref "C24") (pin "2") (pinfunction "2_2") (pintype "passive"))
      (node (ref "C26") (pin "1") (pinfunction "1_1") (pintype "passive"))
      (node (ref "C7") (pin "1") (pinfunction "1_1") (pintype "passive"))
      (node (ref "C9") (pin "2") (pinfunction "2_2") (pintype "passive"))
      (node (ref "MK1") (pin "2") (pinfunction "SELECT_2") (pintype "input"))
      (node (ref "MK1") (pin "5") (pinfunction "VDD_5") (pintype "power_in"))
      (node (ref "MK2") (pin "5") (pinfunction "VDD_5") (pintype "power_in"))
      (node (ref "R10") (pin "2") (pinfunction "2_2") (pintype "passive"))
      (node (ref "R11") (pin "2") (pinfunction "2_2") (pintype "passive"))
      (node (ref "R12") (pin "2") (pinfunction "2_2") (pintype "passive"))
      (node (ref "R13") (pin "2") (pinfunction "2_2") (pintype "passive"))
      (node (ref "R14") (pin "2") (pinfunction "2_2") (pintype "passive"))
      (node (ref "R9") (pin "2") (pinfunction "2_2") (pintype "passive"))
      (node (ref "RN1") (pin "7") (pintype "passive"))
      (node (ref "RN1") (pin "8") (pintype "passive"))
      (node (ref "U1") (pin "8") (pinfunction "VCCB_8") (pintype "power_in"))
      (node (ref "U2") (pin "18") (pinfunction "VCCB_2_18") (pintype "passive"))
      (node (ref "U2") (pin "7") (pinfunction "VCCB_1_7") (pintype "passive"))
      (node (ref "U4") (pin "3") (pinfunction "VIN_3") (pintype "power_in"))
      (node (ref "U5") (pin "3") (pinfunction "VIN_3") (pintype "power_in"))
      (node (ref "U6") (pin "3") (pinfunction "VIN_3") (pintype "power_in"))
      (node (ref "U7") (pin "8") (pinfunction "VccB_8") (pintype "power_in"))
      (node (ref "UPDuino1") (pin "1") (pinfunction "3.3V_1") (pintype "passive"))
    )
    (net (code "70") (name "unconnected-(U4-NC-Pad5)") (class "Default")
      (node (ref "U4") (pin "5") (pinfunction "NC_5") (pintype "passive"))
    )
    (net (code "71") (name "unconnected-(U5-NC-Pad5)") (class "Default")
      (node (ref "U5") (pin "5") (pinfunction "NC_5") (pintype "passive"))
    )
    (net (code "72") (name "unconnected-(U6-NC-Pad5)") (class "Default")
      (node (ref "U6") (pin "5") (pinfunction "NC_5") (pintype "passive"))
    )
    (net (code "73") (name "unconnected-(Z_FDM1-Pad1)") (class "Default")
      (node (ref "Z_FDM1") (pin "1") (pinfunction "1_1") (pintype "passive"))
    )
    (net (code "74") (name "unconnected-(Z_FDM2-Pad1)") (class "Default")
      (node (ref "Z_FDM2") (pin "1") (pinfunction "1_1") (pintype "passive"))
    )
    (net (code "75") (name "unconnected-(Z_FDM3-Pad1)") (class "Default")
      (node (ref "Z_FDM3") (pin "1") (pinfunction "1_1") (pintype "passive"))
    )
    (net (code "76") (name "unconnected-(Z_FDM4-Pad1)") (class "Default")
      (node (ref "Z_FDM4") (pin "1") (pinfunction "1_1") (pintype "passive"))
    )
    (net (code "77") (name "unconnected-(Z_FDM5-Pad1)") (class "Default")
      (node (ref "Z_FDM5") (pin "1") (pinfunction "1_1") (pintype "passive"))
    )
    (net (code "78") (name "unconnected-(Z_FDM6-Pad1)") (class "Default")
      (node (ref "Z_FDM6") (pin "1") (pinfunction "1_1") (pintype "passive"))
    )
  )
)
